# emilyBoard.net
KiCad netlist of a schematic drawn in EAGLE
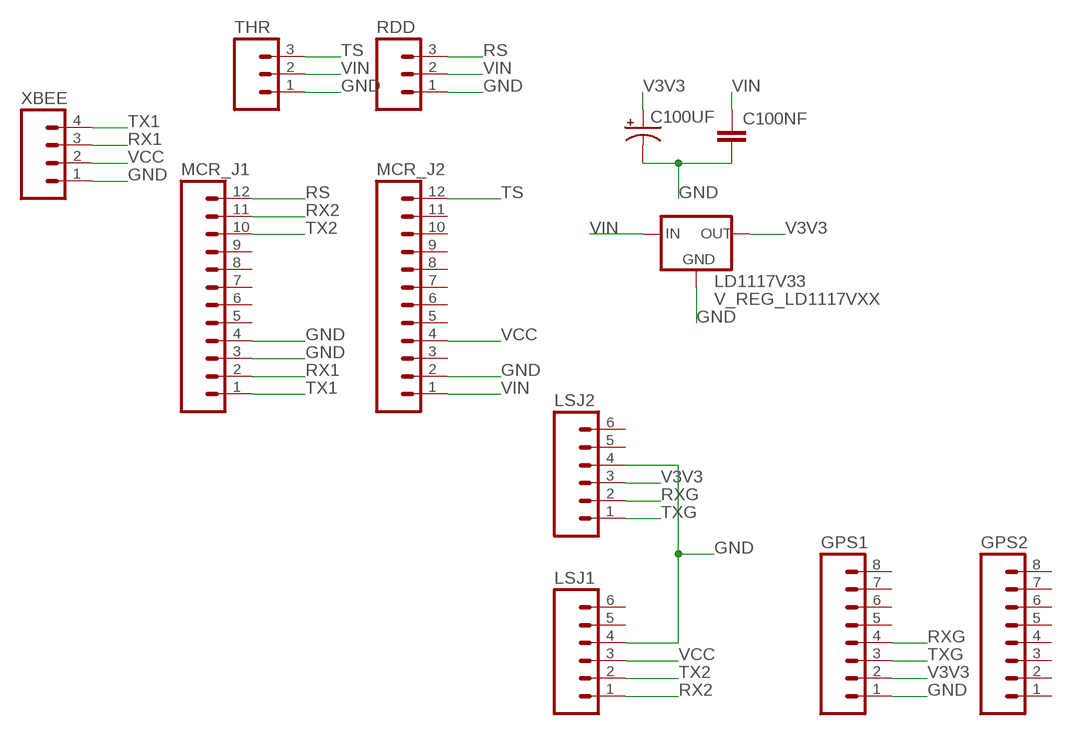
[diagram p0: schematic, sheet 1]

(export (version "E")
  (design (tool "Eeschema 10.0.6"))
  (components
    (comp (ref "C100NF")
      (value "CAPEZ")
      (footprint "eagle-import:CAP-PTH-SMALLEZ")
      (libsource (lib "eagle-import") (part "CAPEZ"))
    )
    (comp (ref "C100UF")
      (value "CAP_POLPTH1")
      (footprint "eagle-import:CPOL-RADIAL-100UF-25V")
      (libsource (lib "eagle-import") (part "CAP_POLPTH1"))
    )
    (comp (ref "GPS1")
      (value "M08")
      (footprint "eagle-import:1X08_ROUND")
      (libsource (lib "eagle-import") (part "M08"))
    )
    (comp (ref "GPS2")
      (value "M08")
      (footprint "eagle-import:1X08_ROUND")
      (libsource (lib "eagle-import") (part "M08"))
    )
    (comp (ref "LD1117V33")
      (value "V_REG_LD1117VXX")
      (footprint "eagle-import:78XXL")
      (libsource (lib "eagle-import") (part "V_REG_LD1117VXX"))
    )
    (comp (ref "LSJ1")
      (value "M06NO_SILK_FEMALE_PTH")
      (footprint "eagle-import:1X06_NO_SILK")
      (libsource (lib "eagle-import") (part "M06NO_SILK_FEMALE_PTH"))
    )
    (comp (ref "LSJ2")
      (value "M06NO_SILK_FEMALE_PTH")
      (footprint "eagle-import:1X06_NO_SILK")
      (libsource (lib "eagle-import") (part "M06NO_SILK_FEMALE_PTH"))
    )
    (comp (ref "MCR_J1")
      (value "M12PTH")
      (footprint "eagle-import:1X12")
      (libsource (lib "eagle-import") (part "M12PTH"))
    )
    (comp (ref "MCR_J2")
      (value "M12PTH")
      (footprint "eagle-import:1X12")
      (libsource (lib "eagle-import") (part "M12PTH"))
    )
    (comp (ref "RDD")
      (value "M03PTH")
      (footprint "eagle-import:1X03")
      (libsource (lib "eagle-import") (part "M03PTH"))
    )
    (comp (ref "THR")
      (value "M03PTH")
      (footprint "eagle-import:1X03")
      (libsource (lib "eagle-import") (part "M03PTH"))
    )
    (comp (ref "XBEE")
      (value "M04PTH")
      (footprint "eagle-import:1X04")
      (libsource (lib "eagle-import") (part "M04PTH"))
    )
  )
  (nets
    (net (code "1") (name "/GND") (class "Default")
      (node (ref "C100NF") (pin "2") (pinfunction "2_2") (pintype "passive"))
      (node (ref "C100UF") (pin "2") (pinfunction "-_2") (pintype "passive"))
      (node (ref "GPS1") (pin "1") (pinfunction "1_1") (pintype "passive"))
      (node (ref "LD1117V33") (pin "IN") (pinfunction "GND_IN") (pintype "input"))
      (node (ref "LSJ1") (pin "4") (pinfunction "4_4") (pintype "passive"))
      (node (ref "LSJ2") (pin "4") (pinfunction "4_4") (pintype "passive"))
      (node (ref "MCR_J1") (pin "3") (pinfunction "3_3") (pintype "passive"))
      (node (ref "MCR_J1") (pin "4") (pinfunction "4_4") (pintype "passive"))
      (node (ref "MCR_J2") (pin "2") (pinfunction "2_2") (pintype "passive"))
      (node (ref "RDD") (pin "1") (pinfunction "1_1") (pintype "passive"))
      (node (ref "THR") (pin "1") (pinfunction "1_1") (pintype "passive"))
      (node (ref "XBEE") (pin "1") (pinfunction "1_1") (pintype "passive"))
    )
    (net (code "2") (name "/RS") (class "Default")
      (node (ref "MCR_J1") (pin "12") (pinfunction "12_12") (pintype "passive"))
      (node (ref "RDD") (pin "3") (pinfunction "3_3") (pintype "passive"))
    )
    (net (code "3") (name "/RX1") (class "Default")
      (node (ref "MCR_J1") (pin "2") (pinfunction "2_2") (pintype "passive"))
      (node (ref "XBEE") (pin "3") (pinfunction "3_3") (pintype "passive"))
    )
    (net (code "4") (name "/RX2") (class "Default")
      (node (ref "LSJ1") (pin "1") (pinfunction "1_1") (pintype "passive"))
      (node (ref "MCR_J1") (pin "11") (pinfunction "11_11") (pintype "passive"))
    )
    (net (code "5") (name "/RXG") (class "Default")
      (node (ref "GPS1") (pin "4") (pinfunction "4_4") (pintype "passive"))
      (node (ref "LSJ2") (pin "2") (pinfunction "2_2") (pintype "passive"))
    )
    (net (code "6") (name "/TS") (class "Default")
      (node (ref "MCR_J2") (pin "12") (pinfunction "12_12") (pintype "passive"))
      (node (ref "THR") (pin "3") (pinfunction "3_3") (pintype "passive"))
    )
    (net (code "7") (name "/TX1") (class "Default")
      (node (ref "MCR_J1") (pin "1") (pinfunction "1_1") (pintype "passive"))
      (node (ref "XBEE") (pin "4") (pinfunction "4_4") (pintype "passive"))
    )
    (net (code "8") (name "/TX2") (class "Default")
      (node (ref "LSJ1") (pin "2") (pinfunction "2_2") (pintype "passive"))
      (node (ref "MCR_J1") (pin "10") (pinfunction "10_10") (pintype "passive"))
    )
    (net (code "9") (name "/TXG") (class "Default")
      (node (ref "GPS1") (pin "3") (pinfunction "3_3") (pintype "passive"))
      (node (ref "LSJ2") (pin "1") (pinfunction "1_1") (pintype "passive"))
    )
    (net (code "10") (name "/V3V3") (class "Default")
      (node (ref "C100UF") (pin "1") (pinfunction "+_1") (pintype "passive"))
      (node (ref "GPS1") (pin "2") (pinfunction "2_2") (pintype "passive"))
      (node (ref "LD1117V33") (pin "GND") (pinfunction "OUT_GND") (pintype "passive"))
      (node (ref "LSJ2") (pin "3") (pinfunction "3_3") (pintype "passive"))
    )
    (net (code "11") (name "/VCC") (class "Default")
      (node (ref "LSJ1") (pin "3") (pinfunction "3_3") (pintype "passive"))
      (node (ref "MCR_J2") (pin "4") (pinfunction "4_4") (pintype "passive"))
      (node (ref "XBEE") (pin "2") (pinfunction "2_2") (pintype "passive"))
    )
    (net (code "12") (name "/VIN") (class "Default")
      (node (ref "C100NF") (pin "1") (pinfunction "1_1") (pintype "passive"))
      (node (ref "LD1117V33") (pin "OUT") (pinfunction "IN_OUT") (pintype "input"))
      (node (ref "MCR_J2") (pin "1") (pinfunction "1_1") (pintype "passive"))
      (node (ref "RDD") (pin "2") (pinfunction "2_2") (pintype "passive"))
      (node (ref "THR") (pin "2") (pinfunction "2_2") (pintype "passive"))
    )
    (net (code "13") (name "unconnected-(GPS1-Pad5)") (class "Default")
      (node (ref "GPS1") (pin "5") (pinfunction "5_5") (pintype "passive"))
    )
    (net (code "14") (name "unconnected-(GPS1-Pad6)") (class "Default")
      (node (ref "GPS1") (pin "6") (pinfunction "6_6") (pintype "passive"))
    )
    (net (code "15") (name "unconnected-(GPS1-Pad7)") (class "Default")
      (node (ref "GPS1") (pin "7") (pinfunction "7_7") (pintype "passive"))
    )
    (net (code "16") (name "unconnected-(GPS1-Pad8)") (class "Default")
      (node (ref "GPS1") (pin "8") (pinfunction "8_8") (pintype "passive"))
    )
    (net (code "17") (name "unconnected-(GPS2-Pad1)") (class "Default")
      (node (ref "GPS2") (pin "1") (pinfunction "1_1") (pintype "passive"))
    )
    (net (code "18") (name "unconnected-(GPS2-Pad2)") (class "Default")
      (node (ref "GPS2") (pin "2") (pinfunction "2_2") (pintype "passive"))
    )
    (net (code "19") (name "unconnected-(GPS2-Pad3)") (class "Default")
      (node (ref "GPS2") (pin "3") (pinfunction "3_3") (pintype "passive"))
    )
    (net (code "20") (name "unconnected-(GPS2-Pad4)") (class "Default")
      (node (ref "GPS2") (pin "4") (pinfunction "4_4") (pintype "passive"))
    )
    (net (code "21") (name "unconnected-(GPS2-Pad5)") (class "Default")
      (node (ref "GPS2") (pin "5") (pinfunction "5_5") (pintype "passive"))
    )
    (net (code "22") (name "unconnected-(GPS2-Pad6)") (class "Default")
      (node (ref "GPS2") (pin "6") (pinfunction "6_6") (pintype "passive"))
    )
    (net (code "23") (name "unconnected-(GPS2-Pad7)") (class "Default")
      (node (ref "GPS2") (pin "7") (pinfunction "7_7") (pintype "passive"))
    )
    (net (code "24") (name "unconnected-(GPS2-Pad8)") (class "Default")
      (node (ref "GPS2") (pin "8") (pinfunction "8_8") (pintype "passive"))
    )
    (net (code "25") (name "unconnected-(LSJ1-Pad5)") (class "Default")
      (node (ref "LSJ1") (pin "5") (pinfunction "5_5") (pintype "passive"))
    )
    (net (code "26") (name "unconnected-(LSJ1-Pad6)") (class "Default")
      (node (ref "LSJ1") (pin "6") (pinfunction "6_6") (pintype "passive"))
    )
    (net (code "27") (name "unconnected-(LSJ2-Pad5)") (class "Default")
      (node (ref "LSJ2") (pin "5") (pinfunction "5_5") (pintype "passive"))
    )
    (net (code "28") (name "unconnected-(LSJ2-Pad6)") (class "Default")
      (node (ref "LSJ2") (pin "6") (pinfunction "6_6") (pintype "passive"))
    )
    (net (code "29") (name "unconnected-(MCR_J1-Pad5)") (class "Default")
      (node (ref "MCR_J1") (pin "5") (pinfunction "5_5") (pintype "passive"))
    )
    (net (code "30") (name "unconnected-(MCR_J1-Pad6)") (class "Default")
      (node (ref "MCR_J1") (pin "6") (pinfunction "6_6") (pintype "passive"))
    )
    (net (code "31") (name "unconnected-(MCR_J1-Pad7)") (class "Default")
      (node (ref "MCR_J1") (pin "7") (pinfunction "7_7") (pintype "passive"))
    )
    (net (code "32") (name "unconnected-(MCR_J1-Pad8)") (class "Default")
      (node (ref "MCR_J1") (pin "8") (pinfunction "8_8") (pintype "passive"))
    )
    (net (code "33") (name "unconnected-(MCR_J1-Pad9)") (class "Default")
      (node (ref "MCR_J1") (pin "9") (pinfunction "9_9") (pintype "passive"))
    )
    (net (code "34") (name "unconnected-(MCR_J2-Pad3)") (class "Default")
      (node (ref "MCR_J2") (pin "3") (pinfunction "3_3") (pintype "passive"))
    )
    (net (code "35") (name "unconnected-(MCR_J2-Pad5)") (class "Default")
      (node (ref "MCR_J2") (pin "5") (pinfunction "5_5") (pintype "passive"))
    )
    (net (code "36") (name "unconnected-(MCR_J2-Pad6)") (class "Default")
      (node (ref "MCR_J2") (pin "6") (pinfunction "6_6") (pintype "passive"))
    )
    (net (code "37") (name "unconnected-(MCR_J2-Pad7)") (class "Default")
      (node (ref "MCR_J2") (pin "7") (pinfunction "7_7") (pintype "passive"))
    )
    (net (code "38") (name "unconnected-(MCR_J2-Pad8)") (class "Default")
      (node (ref "MCR_J2") (pin "8") (pinfunction "8_8") (pintype "passive"))
    )
    (net (code "39") (name "unconnected-(MCR_J2-Pad9)") (class "Default")
      (node (ref "MCR_J2") (pin "9") (pinfunction "9_9") (pintype "passive"))
    )
    (net (code "40") (name "unconnected-(MCR_J2-Pad10)") (class "Default")
      (node (ref "MCR_J2") (pin "10") (pinfunction "10_10") (pintype "passive"))
    )
    (net (code "41") (name "unconnected-(MCR_J2-Pad11)") (class "Default")
      (node (ref "MCR_J2") (pin "11") (pinfunction "11_11") (pintype "passive"))
    )
  )
)
